# MKL02Z_breakout.net
KiCad netlist of a schematic drawn in EAGLE
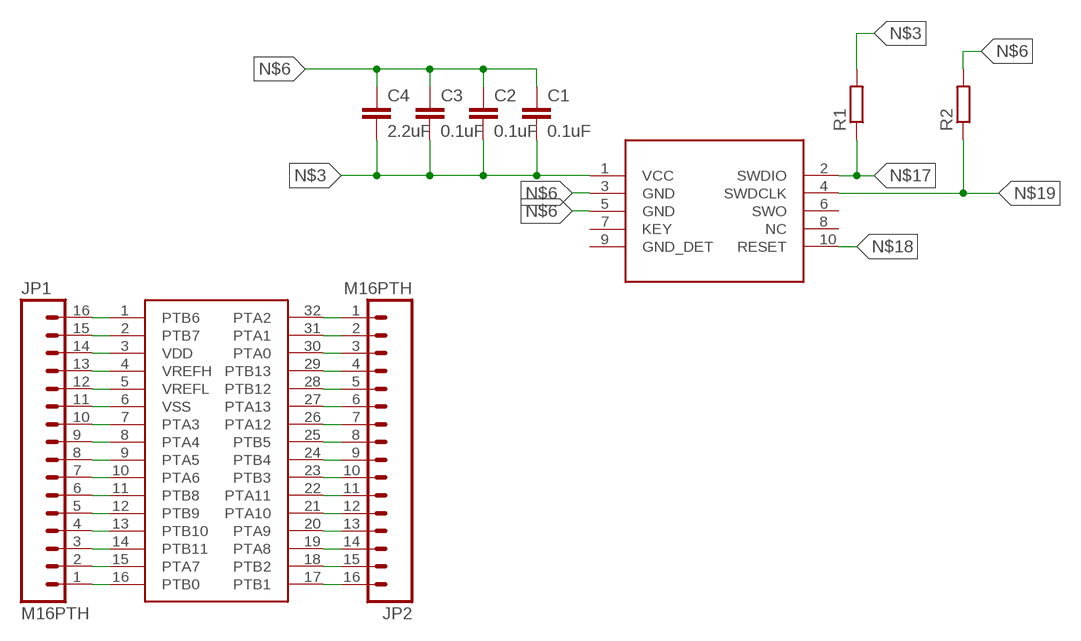
[diagram p0: schematic, sheet 1]

(export (version "E")
  (design (tool "Eeschema 10.0.6"))
  (components
    (comp (ref "C1")
      (value "0.1uF")
      (footprint "eagle-import:C0603")
      (libsource (lib "eagle-import") (part "C-EUC0603"))
    )
    (comp (ref "C2")
      (value "0.1uF")
      (footprint "eagle-import:C0603")
      (libsource (lib "eagle-import") (part "C-EUC0603"))
    )
    (comp (ref "C3")
      (value "0.1uF")
      (footprint "eagle-import:C0603")
      (libsource (lib "eagle-import") (part "C-EUC0603"))
    )
    (comp (ref "C4")
      (value "2.2uF")
      (footprint "eagle-import:C0603")
      (libsource (lib "eagle-import") (part "C-EUC0603"))
    )
    (comp (ref "JP1")
      (value "M16PTH")
      (footprint "eagle-import:1X16")
      (libsource (lib "eagle-import") (part "M16PTH"))
    )
    (comp (ref "JP2")
      (value "M16PTH")
      (footprint "eagle-import:1X16")
      (libsource (lib "eagle-import") (part "M16PTH"))
    )
    (comp (ref "R1")
      (value "R-EU_R0603")
      (footprint "eagle-import:R0603")
      (libsource (lib "eagle-import") (part "R-EU_R0603"))
    )
    (comp (ref "R2")
      (value "R-EU_R0603")
      (footprint "eagle-import:R0603")
      (libsource (lib "eagle-import") (part "R-EU_R0603"))
    )
    (comp (ref "U$1")
      (value "MKL02Z16VFM4")
      (footprint "eagle-import:MKL02Z16VFM4")
      (libsource (lib "eagle-import") (part "MKL02Z16VFM4"))
    )
    (comp (ref "U$2")
      (value "SWD_10_PIN")
      (footprint "eagle-import:SWD_10_PIN")
      (libsource (lib "eagle-import") (part "SWD_10_PIN"))
    )
  )
  (nets
    (net (code "1") (name "N$3") (class "Default")
      (node (ref "C1") (pin "2") (pinfunction "2_2") (pintype "passive"))
      (node (ref "C2") (pin "2") (pinfunction "2_2") (pintype "passive"))
      (node (ref "C3") (pin "2") (pinfunction "2_2") (pintype "passive"))
      (node (ref "C4") (pin "2") (pinfunction "2_2") (pintype "passive"))
      (node (ref "JP1") (pin "14") (pinfunction "14_14") (pintype "passive"))
      (node (ref "R1") (pin "2") (pinfunction "2_2") (pintype "passive"))
      (node (ref "U$1") (pin "3") (pinfunction "VDD_3") (pintype "bidirectional"))
      (node (ref "U$2") (pin "1") (pinfunction "VCC_1") (pintype "bidirectional"))
    )
    (net (code "2") (name "N$6") (class "Default")
      (node (ref "C1") (pin "1") (pinfunction "1_1") (pintype "passive"))
      (node (ref "C2") (pin "1") (pinfunction "1_1") (pintype "passive"))
      (node (ref "C3") (pin "1") (pinfunction "1_1") (pintype "passive"))
      (node (ref "C4") (pin "1") (pinfunction "1_1") (pintype "passive"))
      (node (ref "JP1") (pin "11") (pinfunction "11_11") (pintype "passive"))
      (node (ref "R2") (pin "2") (pinfunction "2_2") (pintype "passive"))
      (node (ref "U$1") (pin "6") (pinfunction "VSS_6") (pintype "bidirectional"))
      (node (ref "U$2") (pin "3") (pinfunction "GND_3") (pintype "bidirectional"))
      (node (ref "U$2") (pin "5") (pinfunction "GND_5") (pintype "bidirectional"))
    )
    (net (code "3") (name "N$17") (class "Default")
      (node (ref "JP2") (pin "1") (pinfunction "1_1") (pintype "passive"))
      (node (ref "R1") (pin "1") (pinfunction "1_1") (pintype "passive"))
      (node (ref "U$1") (pin "32") (pinfunction "PTA2_32") (pintype "bidirectional"))
      (node (ref "U$2") (pin "2") (pinfunction "SWDIO_2") (pintype "bidirectional"))
    )
    (net (code "4") (name "N$18") (class "Default")
      (node (ref "JP2") (pin "2") (pinfunction "2_2") (pintype "passive"))
      (node (ref "U$1") (pin "31") (pinfunction "PTA1_31") (pintype "bidirectional"))
      (node (ref "U$2") (pin "10") (pinfunction "RESET_10") (pintype "bidirectional"))
    )
    (net (code "5") (name "N$19") (class "Default")
      (node (ref "JP2") (pin "3") (pinfunction "3_3") (pintype "passive"))
      (node (ref "R2") (pin "1") (pinfunction "1_1") (pintype "passive"))
      (node (ref "U$1") (pin "30") (pinfunction "PTA0_30") (pintype "bidirectional"))
      (node (ref "U$2") (pin "4") (pinfunction "SWDCLK_4") (pintype "bidirectional"))
    )
    (net (code "6") (name "Net-(U$1-PTA3)") (class "Default")
      (node (ref "JP1") (pin "10") (pinfunction "10_10") (pintype "passive"))
      (node (ref "U$1") (pin "7") (pinfunction "PTA3_7") (pintype "bidirectional"))
    )
    (net (code "7") (name "Net-(U$1-PTA4)") (class "Default")
      (node (ref "JP1") (pin "9") (pinfunction "9_9") (pintype "passive"))
      (node (ref "U$1") (pin "8") (pinfunction "PTA4_8") (pintype "bidirectional"))
    )
    (net (code "8") (name "Net-(U$1-PTA5)") (class "Default")
      (node (ref "JP1") (pin "8") (pinfunction "8_8") (pintype "passive"))
      (node (ref "U$1") (pin "9") (pinfunction "PTA5_9") (pintype "bidirectional"))
    )
    (net (code "9") (name "Net-(U$1-PTA6)") (class "Default")
      (node (ref "JP1") (pin "7") (pinfunction "7_7") (pintype "passive"))
      (node (ref "U$1") (pin "10") (pinfunction "PTA6_10") (pintype "bidirectional"))
    )
    (net (code "10") (name "Net-(U$1-PTA7)") (class "Default")
      (node (ref "JP1") (pin "2") (pinfunction "2_2") (pintype "passive"))
      (node (ref "U$1") (pin "15") (pinfunction "PTA7_15") (pintype "bidirectional"))
    )
    (net (code "11") (name "Net-(U$1-PTA8)") (class "Default")
      (node (ref "JP2") (pin "14") (pinfunction "14_14") (pintype "passive"))
      (node (ref "U$1") (pin "19") (pinfunction "PTA8_19") (pintype "bidirectional"))
    )
    (net (code "12") (name "Net-(U$1-PTA9)") (class "Default")
      (node (ref "JP2") (pin "13") (pinfunction "13_13") (pintype "passive"))
      (node (ref "U$1") (pin "20") (pinfunction "PTA9_20") (pintype "bidirectional"))
    )
    (net (code "13") (name "Net-(U$1-PTA10)") (class "Default")
      (node (ref "JP2") (pin "12") (pinfunction "12_12") (pintype "passive"))
      (node (ref "U$1") (pin "21") (pinfunction "PTA10_21") (pintype "bidirectional"))
    )
    (net (code "14") (name "Net-(U$1-PTA11)") (class "Default")
      (node (ref "JP2") (pin "11") (pinfunction "11_11") (pintype "passive"))
      (node (ref "U$1") (pin "22") (pinfunction "PTA11_22") (pintype "bidirectional"))
    )
    (net (code "15") (name "Net-(U$1-PTA12)") (class "Default")
      (node (ref "JP2") (pin "7") (pinfunction "7_7") (pintype "passive"))
      (node (ref "U$1") (pin "26") (pinfunction "PTA12_26") (pintype "bidirectional"))
    )
    (net (code "16") (name "Net-(U$1-PTA13)") (class "Default")
      (node (ref "JP2") (pin "6") (pinfunction "6_6") (pintype "passive"))
      (node (ref "U$1") (pin "27") (pinfunction "PTA13_27") (pintype "bidirectional"))
    )
    (net (code "17") (name "Net-(U$1-PTB0)") (class "Default")
      (node (ref "JP1") (pin "1") (pinfunction "1_1") (pintype "passive"))
      (node (ref "U$1") (pin "16") (pinfunction "PTB0_16") (pintype "bidirectional"))
    )
    (net (code "18") (name "Net-(U$1-PTB1)") (class "Default")
      (node (ref "JP2") (pin "16") (pinfunction "16_16") (pintype "passive"))
      (node (ref "U$1") (pin "17") (pinfunction "PTB1_17") (pintype "bidirectional"))
    )
    (net (code "19") (name "Net-(U$1-PTB2)") (class "Default")
      (node (ref "JP2") (pin "15") (pinfunction "15_15") (pintype "passive"))
      (node (ref "U$1") (pin "18") (pinfunction "PTB2_18") (pintype "bidirectional"))
    )
    (net (code "20") (name "Net-(U$1-PTB3)") (class "Default")
      (node (ref "JP2") (pin "10") (pinfunction "10_10") (pintype "passive"))
      (node (ref "U$1") (pin "23") (pinfunction "PTB3_23") (pintype "bidirectional"))
    )
    (net (code "21") (name "Net-(U$1-PTB4)") (class "Default")
      (node (ref "JP2") (pin "9") (pinfunction "9_9") (pintype "passive"))
      (node (ref "U$1") (pin "24") (pinfunction "PTB4_24") (pintype "bidirectional"))
    )
    (net (code "22") (name "Net-(U$1-PTB5)") (class "Default")
      (node (ref "JP2") (pin "8") (pinfunction "8_8") (pintype "passive"))
      (node (ref "U$1") (pin "25") (pinfunction "PTB5_25") (pintype "bidirectional"))
    )
    (net (code "23") (name "Net-(U$1-PTB6)") (class "Default")
      (node (ref "JP1") (pin "16") (pinfunction "16_16") (pintype "passive"))
      (node (ref "U$1") (pin "1") (pinfunction "PTB6_1") (pintype "bidirectional"))
    )
    (net (code "24") (name "Net-(U$1-PTB7)") (class "Default")
      (node (ref "JP1") (pin "15") (pinfunction "15_15") (pintype "passive"))
      (node (ref "U$1") (pin "2") (pinfunction "PTB7_2") (pintype "bidirectional"))
    )
    (net (code "25") (name "Net-(U$1-PTB8)") (class "Default")
      (node (ref "JP1") (pin "6") (pinfunction "6_6") (pintype "passive"))
      (node (ref "U$1") (pin "11") (pinfunction "PTB8_11") (pintype "bidirectional"))
    )
    (net (code "26") (name "Net-(U$1-PTB9)") (class "Default")
      (node (ref "JP1") (pin "5") (pinfunction "5_5") (pintype "passive"))
      (node (ref "U$1") (pin "12") (pinfunction "PTB9_12") (pintype "bidirectional"))
    )
    (net (code "27") (name "Net-(U$1-PTB10)") (class "Default")
      (node (ref "JP1") (pin "4") (pinfunction "4_4") (pintype "passive"))
      (node (ref "U$1") (pin "13") (pinfunction "PTB10_13") (pintype "bidirectional"))
    )
    (net (code "28") (name "Net-(U$1-PTB11)") (class "Default")
      (node (ref "JP1") (pin "3") (pinfunction "3_3") (pintype "passive"))
      (node (ref "U$1") (pin "14") (pinfunction "PTB11_14") (pintype "bidirectional"))
    )
    (net (code "29") (name "Net-(U$1-PTB12)") (class "Default")
      (node (ref "JP2") (pin "5") (pinfunction "5_5") (pintype "passive"))
      (node (ref "U$1") (pin "28") (pinfunction "PTB12_28") (pintype "bidirectional"))
    )
    (net (code "30") (name "Net-(U$1-PTB13)") (class "Default")
      (node (ref "JP2") (pin "4") (pinfunction "4_4") (pintype "passive"))
      (node (ref "U$1") (pin "29") (pinfunction "PTB13_29") (pintype "bidirectional"))
    )
    (net (code "31") (name "Net-(U$1-VREFH)") (class "Default")
      (node (ref "JP1") (pin "13") (pinfunction "13_13") (pintype "passive"))
      (node (ref "U$1") (pin "4") (pinfunction "VREFH_4") (pintype "bidirectional"))
    )
    (net (code "32") (name "Net-(U$1-VREFL)") (class "Default")
      (node (ref "JP1") (pin "12") (pinfunction "12_12") (pintype "passive"))
      (node (ref "U$1") (pin "5") (pinfunction "VREFL_5") (pintype "bidirectional"))
    )
    (net (code "33") (name "unconnected-(U$2-GND_DET-Pad9)") (class "Default")
      (node (ref "U$2") (pin "9") (pinfunction "GND_DET_9") (pintype "bidirectional"))
    )
    (net (code "34") (name "unconnected-(U$2-KEY-Pad7)") (class "Default")
      (node (ref "U$2") (pin "7") (pinfunction "KEY_7") (pintype "bidirectional"))
    )
    (net (code "35") (name "unconnected-(U$2-NC-Pad8)") (class "Default")
      (node (ref "U$2") (pin "8") (pinfunction "NC_8") (pintype "bidirectional"))
    )
    (net (code "36") (name "unconnected-(U$2-SWO-Pad6)") (class "Default")
      (node (ref "U$2") (pin "6") (pinfunction "SWO_6") (pintype "bidirectional"))
    )
  )
)
